# MocoMoco.net
KiCad netlist of a schematic drawn in EAGLE
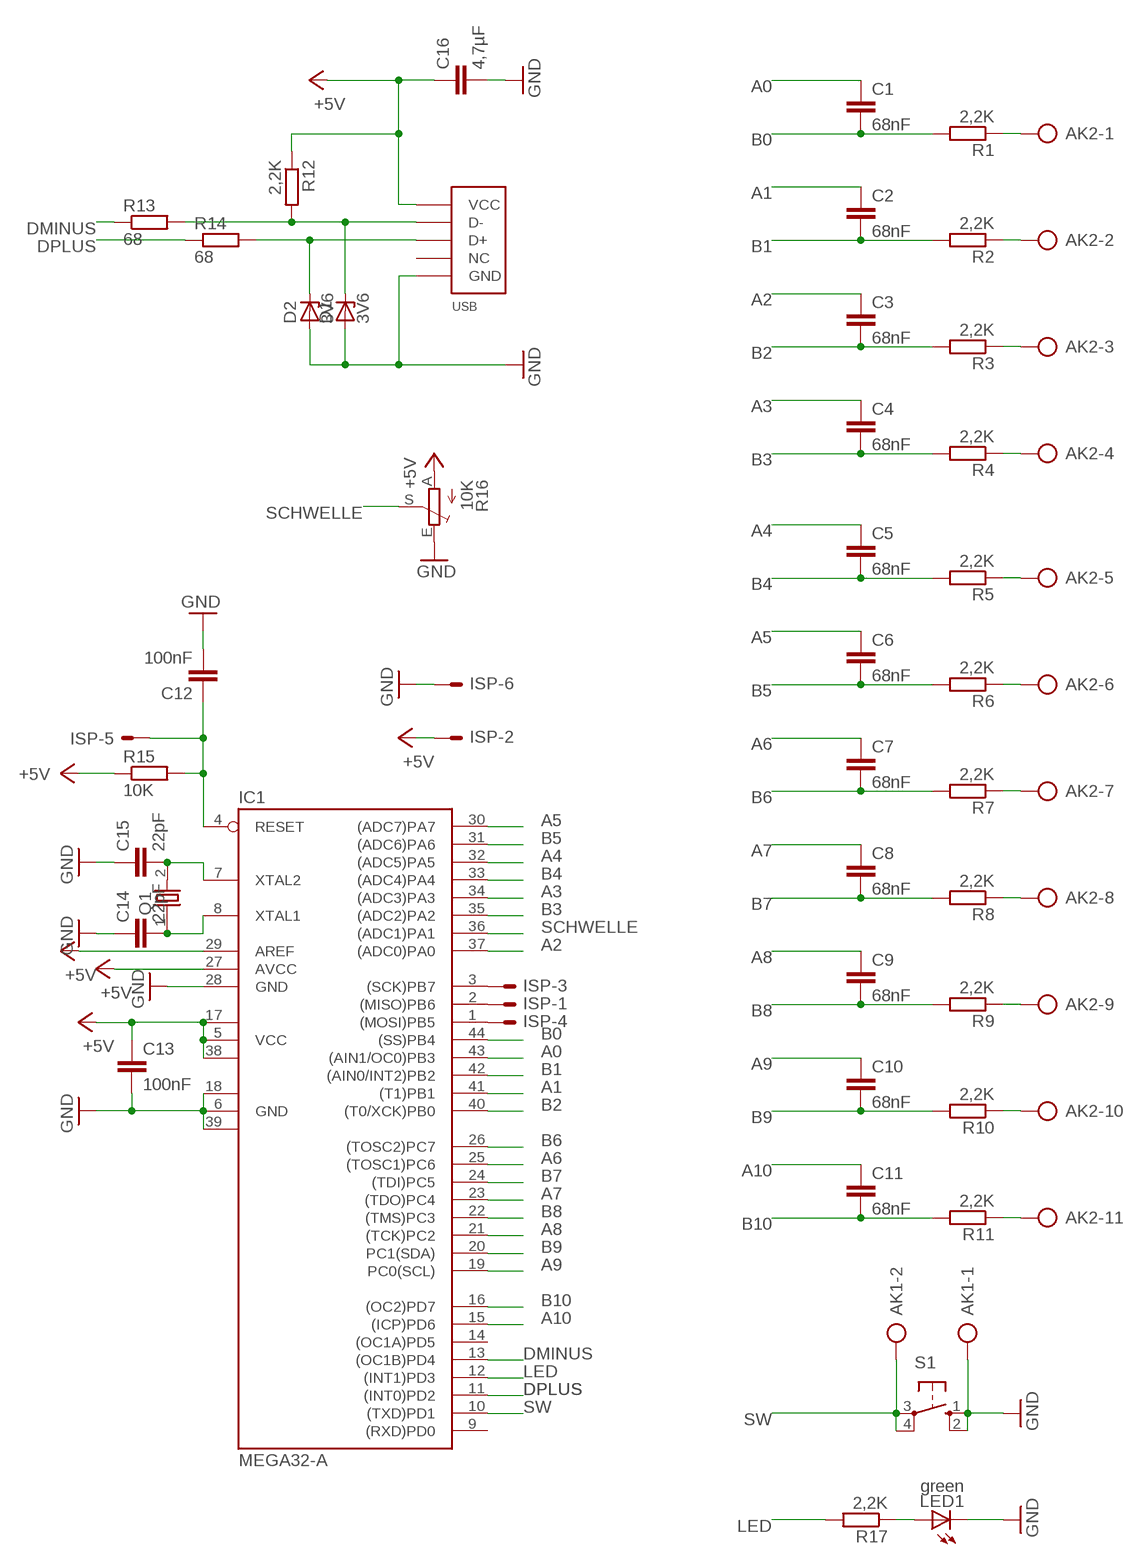
[diagram p0: schematic, sheet 1]

(export (version "E")
  (design (tool "Eeschema 10.0.6"))
  (components
    (comp (ref "AK1")
      (value "AK2")
      (footprint "eagle-import:AK_2")
      (libsource (lib "eagle-import") (part "AK2"))
    )
    (comp (ref "AK2")
      (value "AK11")
      (footprint "eagle-import:AK_11")
      (libsource (lib "eagle-import") (part "AK11"))
    )
    (comp (ref "C1")
      (value "68nF")
      (footprint "eagle-import:C0805K")
      (libsource (lib "eagle-import") (part "C-EUC0805K"))
    )
    (comp (ref "C2")
      (value "68nF")
      (footprint "eagle-import:C0805K")
      (libsource (lib "eagle-import") (part "C-EUC0805K"))
    )
    (comp (ref "C3")
      (value "68nF")
      (footprint "eagle-import:C0805K")
      (libsource (lib "eagle-import") (part "C-EUC0805K"))
    )
    (comp (ref "C4")
      (value "68nF")
      (footprint "eagle-import:C0805K")
      (libsource (lib "eagle-import") (part "C-EUC0805K"))
    )
    (comp (ref "C5")
      (value "68nF")
      (footprint "eagle-import:C0805K")
      (libsource (lib "eagle-import") (part "C-EUC0805K"))
    )
    (comp (ref "C6")
      (value "68nF")
      (footprint "eagle-import:C0805K")
      (libsource (lib "eagle-import") (part "C-EUC0805K"))
    )
    (comp (ref "C7")
      (value "68nF")
      (footprint "eagle-import:C0805K")
      (libsource (lib "eagle-import") (part "C-EUC0805K"))
    )
    (comp (ref "C8")
      (value "68nF")
      (footprint "eagle-import:C0805K")
      (libsource (lib "eagle-import") (part "C-EUC0805K"))
    )
    (comp (ref "C9")
      (value "68nF")
      (footprint "eagle-import:C0805K")
      (libsource (lib "eagle-import") (part "C-EUC0805K"))
    )
    (comp (ref "C10")
      (value "68nF")
      (footprint "eagle-import:C0805K")
      (libsource (lib "eagle-import") (part "C-EUC0805K"))
    )
    (comp (ref "C11")
      (value "68nF")
      (footprint "eagle-import:C0805K")
      (libsource (lib "eagle-import") (part "C-EUC0805K"))
    )
    (comp (ref "C12")
      (value "100nF")
      (footprint "eagle-import:C0805K")
      (libsource (lib "eagle-import") (part "C-EUC0805K"))
    )
    (comp (ref "C13")
      (value "100nF")
      (footprint "eagle-import:C0805K")
      (libsource (lib "eagle-import") (part "C-EUC0805K"))
    )
    (comp (ref "C14")
      (value "22pF")
      (footprint "eagle-import:C0805K")
      (libsource (lib "eagle-import") (part "C-EUC0805K"))
    )
    (comp (ref "C15")
      (value "22pF")
      (footprint "eagle-import:C0805K")
      (libsource (lib "eagle-import") (part "C-EUC0805K"))
    )
    (comp (ref "C16")
      (value "4,7µF")
      (footprint "eagle-import:C3216")
      (libsource (lib "eagle-import") (part "C-EUC3216"))
    )
    (comp (ref "D1")
      (value "3V6")
      (footprint "eagle-import:TO236")
      (libsource (lib "eagle-import") (part "BZX84CSMD"))
    )
    (comp (ref "D2")
      (value "3V6")
      (footprint "eagle-import:TO236")
      (libsource (lib "eagle-import") (part "BZX84CSMD"))
    )
    (comp (ref "IC1")
      (value "MEGA32-A")
      (footprint "eagle-import:TQFP44")
      (fields (field (name "MPN") "ATMEGA32-16AU"))
      (libsource (lib "eagle-import") (part "MEGA32-A"))
    )
    (comp (ref "ISP")
      (value "ML6E")
      (footprint "eagle-import:ML6")
      (libsource (lib "eagle-import") (part "ML6E"))
    )
    (comp (ref "LED1")
      (value "green")
      (footprint "eagle-import:CHIP-LED0603")
      (libsource (lib "eagle-import") (part "LEDCHIP-LED0603"))
    )
    (comp (ref "Q1")
      (value "HC-49/US")
      (footprint "eagle-import:HC49UP")
      (libsource (lib "eagle-import") (part "HC-49/US"))
    )
    (comp (ref "R1")
      (value "2,2K")
      (footprint "eagle-import:R0603")
      (libsource (lib "eagle-import") (part "R-EUR0603"))
    )
    (comp (ref "R2")
      (value "2,2K")
      (footprint "eagle-import:R0603")
      (libsource (lib "eagle-import") (part "R-EUR0603"))
    )
    (comp (ref "R3")
      (value "2,2K")
      (footprint "eagle-import:R0603")
      (libsource (lib "eagle-import") (part "R-EUR0603"))
    )
    (comp (ref "R4")
      (value "2,2K")
      (footprint "eagle-import:R0603")
      (libsource (lib "eagle-import") (part "R-EUR0603"))
    )
    (comp (ref "R5")
      (value "2,2K")
      (footprint "eagle-import:R0603")
      (libsource (lib "eagle-import") (part "R-EUR0603"))
    )
    (comp (ref "R6")
      (value "2,2K")
      (footprint "eagle-import:R0603")
      (libsource (lib "eagle-import") (part "R-EUR0603"))
    )
    (comp (ref "R7")
      (value "2,2K")
      (footprint "eagle-import:R0603")
      (libsource (lib "eagle-import") (part "R-EUR0603"))
    )
    (comp (ref "R8")
      (value "2,2K")
      (footprint "eagle-import:R0603")
      (libsource (lib "eagle-import") (part "R-EUR0603"))
    )
    (comp (ref "R9")
      (value "2,2K")
      (footprint "eagle-import:R0603")
      (libsource (lib "eagle-import") (part "R-EUR0603"))
    )
    (comp (ref "R10")
      (value "2,2K")
      (footprint "eagle-import:R0603")
      (libsource (lib "eagle-import") (part "R-EUR0603"))
    )
    (comp (ref "R11")
      (value "2,2K")
      (footprint "eagle-import:R0603")
      (libsource (lib "eagle-import") (part "R-EUR0603"))
    )
    (comp (ref "R12")
      (value "2,2K")
      (footprint "eagle-import:R0603")
      (libsource (lib "eagle-import") (part "R-EUR0603"))
    )
    (comp (ref "R13")
      (value "68")
      (footprint "eagle-import:R0603")
      (libsource (lib "eagle-import") (part "R-EUR0603"))
    )
    (comp (ref "R14")
      (value "68")
      (footprint "eagle-import:R0603")
      (libsource (lib "eagle-import") (part "R-EUR0603"))
    )
    (comp (ref "R15")
      (value "10K")
      (footprint "eagle-import:R0603")
      (libsource (lib "eagle-import") (part "R-EUR0603"))
    )
    (comp (ref "R16")
      (value "10K")
      (footprint "eagle-import:LI10")
      (libsource (lib "eagle-import") (part "TRIM_EU-LI10"))
    )
    (comp (ref "R17")
      (value "2,2K")
      (footprint "eagle-import:R0603")
      (libsource (lib "eagle-import") (part "R-EUR0603"))
    )
    (comp (ref "S1")
      (value "10-XX")
      (footprint "eagle-import:B3F-10XX")
      (fields (field (name "MPN") "B3F-1000"))
      (libsource (lib "eagle-import") (part "10-XX"))
    )
    (comp (ref "USB")
      (value "MICRO_USB")
      (footprint "eagle-import:MICRO_USB_A01SB141B1-292")
      (libsource (lib "eagle-import") (part "MICRO_USB"))
    )
  )
  (nets
    (net (code "1") (name "+5V") (class "Default")
      (node (ref "C13") (pin "1") (pinfunction "1_1") (pintype "passive"))
      (node (ref "C16") (pin "1") (pinfunction "1_1") (pintype "passive"))
      (node (ref "IC1") (pin "17") (pinfunction "VCC1_17") (pintype "power_in"))
      (node (ref "IC1") (pin "27") (pinfunction "AVCC_27") (pintype "power_in"))
      (node (ref "IC1") (pin "29") (pinfunction "AREF_29") (pintype "passive"))
      (node (ref "IC1") (pin "38") (pinfunction "VCC2_38") (pintype "power_in"))
      (node (ref "IC1") (pin "5") (pinfunction "VCC_5") (pintype "power_in"))
      (node (ref "ISP") (pin "2") (pinfunction "S_2") (pintype "passive"))
      (node (ref "R12") (pin "1") (pinfunction "1_1") (pintype "passive"))
      (node (ref "R15") (pin "1") (pinfunction "1_1") (pintype "passive"))
      (node (ref "R16") (pin "A") (pinfunction "A_A") (pintype "passive"))
      (node (ref "USB") (pin "P$1") (pinfunction "VCC_P$1") (pintype "bidirectional"))
    )
    (net (code "2") (name "/A0") (class "Default")
      (node (ref "C1") (pin "1") (pinfunction "1_1") (pintype "passive"))
      (node (ref "IC1") (pin "43") (pinfunction "(AIN1/OC0)PB3_43") (pintype "bidirectional"))
    )
    (net (code "3") (name "/A1") (class "Default")
      (node (ref "C2") (pin "1") (pinfunction "1_1") (pintype "passive"))
      (node (ref "IC1") (pin "41") (pinfunction "(T1)PB1_41") (pintype "bidirectional"))
    )
    (net (code "4") (name "/A2") (class "Default")
      (node (ref "C3") (pin "1") (pinfunction "1_1") (pintype "passive"))
      (node (ref "IC1") (pin "37") (pinfunction "(ADC0)PA0_37") (pintype "bidirectional"))
    )
    (net (code "5") (name "/A3") (class "Default")
      (node (ref "C4") (pin "1") (pinfunction "1_1") (pintype "passive"))
      (node (ref "IC1") (pin "34") (pinfunction "(ADC3)PA3_34") (pintype "bidirectional"))
    )
    (net (code "6") (name "/A4") (class "Default")
      (node (ref "C5") (pin "1") (pinfunction "1_1") (pintype "passive"))
      (node (ref "IC1") (pin "32") (pinfunction "(ADC5)PA5_32") (pintype "bidirectional"))
    )
    (net (code "7") (name "/A5") (class "Default")
      (node (ref "C6") (pin "1") (pinfunction "1_1") (pintype "passive"))
      (node (ref "IC1") (pin "30") (pinfunction "(ADC7)PA7_30") (pintype "bidirectional"))
    )
    (net (code "8") (name "/A6") (class "Default")
      (node (ref "C7") (pin "1") (pinfunction "1_1") (pintype "passive"))
      (node (ref "IC1") (pin "25") (pinfunction "(TOSC1)PC6_25") (pintype "bidirectional"))
    )
    (net (code "9") (name "/A7") (class "Default")
      (node (ref "C8") (pin "1") (pinfunction "1_1") (pintype "passive"))
      (node (ref "IC1") (pin "23") (pinfunction "(TDO)PC4_23") (pintype "bidirectional"))
    )
    (net (code "10") (name "/A8") (class "Default")
      (node (ref "C9") (pin "1") (pinfunction "1_1") (pintype "passive"))
      (node (ref "IC1") (pin "21") (pinfunction "(TCK)PC2_21") (pintype "bidirectional"))
    )
    (net (code "11") (name "/A9") (class "Default")
      (node (ref "C10") (pin "1") (pinfunction "1_1") (pintype "passive"))
      (node (ref "IC1") (pin "19") (pinfunction "PC0(SCL)_19") (pintype "bidirectional"))
    )
    (net (code "12") (name "/A10") (class "Default")
      (node (ref "C11") (pin "1") (pinfunction "1_1") (pintype "passive"))
      (node (ref "IC1") (pin "15") (pinfunction "(ICP)PD6_15") (pintype "bidirectional"))
    )
    (net (code "13") (name "/B0") (class "Default")
      (node (ref "C1") (pin "2") (pinfunction "2_2") (pintype "passive"))
      (node (ref "IC1") (pin "44") (pinfunction "(SS)PB4_44") (pintype "bidirectional"))
      (node (ref "R1") (pin "2") (pinfunction "2_2") (pintype "passive"))
    )
    (net (code "14") (name "/B1") (class "Default")
      (node (ref "C2") (pin "2") (pinfunction "2_2") (pintype "passive"))
      (node (ref "IC1") (pin "42") (pinfunction "(AIN0/INT2)PB2_42") (pintype "bidirectional"))
      (node (ref "R2") (pin "2") (pinfunction "2_2") (pintype "passive"))
    )
    (net (code "15") (name "/B2") (class "Default")
      (node (ref "C3") (pin "2") (pinfunction "2_2") (pintype "passive"))
      (node (ref "IC1") (pin "40") (pinfunction "(T0/XCK)PB0_40") (pintype "bidirectional"))
      (node (ref "R3") (pin "2") (pinfunction "2_2") (pintype "passive"))
    )
    (net (code "16") (name "/B3") (class "Default")
      (node (ref "C4") (pin "2") (pinfunction "2_2") (pintype "passive"))
      (node (ref "IC1") (pin "35") (pinfunction "(ADC2)PA2_35") (pintype "bidirectional"))
      (node (ref "R4") (pin "2") (pinfunction "2_2") (pintype "passive"))
    )
    (net (code "17") (name "/B4") (class "Default")
      (node (ref "C5") (pin "2") (pinfunction "2_2") (pintype "passive"))
      (node (ref "IC1") (pin "33") (pinfunction "(ADC4)PA4_33") (pintype "bidirectional"))
      (node (ref "R5") (pin "2") (pinfunction "2_2") (pintype "passive"))
    )
    (net (code "18") (name "/B5") (class "Default")
      (node (ref "C6") (pin "2") (pinfunction "2_2") (pintype "passive"))
      (node (ref "IC1") (pin "31") (pinfunction "(ADC6)PA6_31") (pintype "bidirectional"))
      (node (ref "R6") (pin "2") (pinfunction "2_2") (pintype "passive"))
    )
    (net (code "19") (name "/B6") (class "Default")
      (node (ref "C7") (pin "2") (pinfunction "2_2") (pintype "passive"))
      (node (ref "IC1") (pin "26") (pinfunction "(TOSC2)PC7_26") (pintype "bidirectional"))
      (node (ref "R7") (pin "2") (pinfunction "2_2") (pintype "passive"))
    )
    (net (code "20") (name "/B7") (class "Default")
      (node (ref "C8") (pin "2") (pinfunction "2_2") (pintype "passive"))
      (node (ref "IC1") (pin "24") (pinfunction "(TDI)PC5_24") (pintype "bidirectional"))
      (node (ref "R8") (pin "2") (pinfunction "2_2") (pintype "passive"))
    )
    (net (code "21") (name "/B8") (class "Default")
      (node (ref "C9") (pin "2") (pinfunction "2_2") (pintype "passive"))
      (node (ref "IC1") (pin "22") (pinfunction "(TMS)PC3_22") (pintype "bidirectional"))
      (node (ref "R9") (pin "2") (pinfunction "2_2") (pintype "passive"))
    )
    (net (code "22") (name "/B9") (class "Default")
      (node (ref "C10") (pin "2") (pinfunction "2_2") (pintype "passive"))
      (node (ref "IC1") (pin "20") (pinfunction "PC1(SDA)_20") (pintype "bidirectional"))
      (node (ref "R10") (pin "2") (pinfunction "2_2") (pintype "passive"))
    )
    (net (code "23") (name "/B10") (class "Default")
      (node (ref "C11") (pin "2") (pinfunction "2_2") (pintype "passive"))
      (node (ref "IC1") (pin "16") (pinfunction "(OC2)PD7_16") (pintype "bidirectional"))
      (node (ref "R11") (pin "2") (pinfunction "2_2") (pintype "passive"))
    )
    (net (code "24") (name "/DMINUS") (class "Default")
      (node (ref "IC1") (pin "13") (pinfunction "(OC1B)PD4_13") (pintype "bidirectional"))
      (node (ref "R13") (pin "1") (pinfunction "1_1") (pintype "passive"))
    )
    (net (code "25") (name "/DPLUS") (class "Default")
      (node (ref "IC1") (pin "11") (pinfunction "(INT0)PD2_11") (pintype "bidirectional"))
      (node (ref "R14") (pin "1") (pinfunction "1_1") (pintype "passive"))
    )
    (net (code "26") (name "/LED") (class "Default")
      (node (ref "IC1") (pin "12") (pinfunction "(INT1)PD3_12") (pintype "bidirectional"))
      (node (ref "R17") (pin "2") (pinfunction "2_2") (pintype "passive"))
    )
    (net (code "27") (name "/SCHWELLE") (class "Default")
      (node (ref "IC1") (pin "36") (pinfunction "(ADC1)PA1_36") (pintype "bidirectional"))
      (node (ref "R16") (pin "S") (pinfunction "S_S") (pintype "passive"))
    )
    (net (code "28") (name "/SW") (class "Default")
      (node (ref "AK1") (pin "2") (pinfunction "KL_2") (pintype "passive"))
      (node (ref "IC1") (pin "10") (pinfunction "(TXD)PD1_10") (pintype "bidirectional"))
      (node (ref "S1") (pin "3") (pinfunction "P_3") (pintype "passive"))
      (node (ref "S1") (pin "4") (pinfunction "P1_4") (pintype "passive"))
    )
    (net (code "29") (name "GND") (class "Default")
      (node (ref "AK1") (pin "1") (pinfunction "KL_1") (pintype "passive"))
      (node (ref "C12") (pin "2") (pinfunction "2_2") (pintype "passive"))
      (node (ref "C13") (pin "2") (pinfunction "2_2") (pintype "passive"))
      (node (ref "C14") (pin "1") (pinfunction "1_1") (pintype "passive"))
      (node (ref "C15") (pin "1") (pinfunction "1_1") (pintype "passive"))
      (node (ref "C16") (pin "2") (pinfunction "2_2") (pintype "passive"))
      (node (ref "D1") (pin "A") (pinfunction "A_A") (pintype "passive"))
      (node (ref "D2") (pin "A") (pinfunction "A_A") (pintype "passive"))
      (node (ref "IC1") (pin "18") (pinfunction "GND1_18") (pintype "power_in"))
      (node (ref "IC1") (pin "28") (pinfunction "GND_28") (pintype "power_in"))
      (node (ref "IC1") (pin "39") (pinfunction "GND2_39") (pintype "power_in"))
      (node (ref "IC1") (pin "6") (pinfunction "GND_6") (pintype "power_in"))
      (node (ref "ISP") (pin "6") (pinfunction "S_6") (pintype "passive"))
      (node (ref "LED1") (pin "C") (pinfunction "C_C") (pintype "passive"))
      (node (ref "R16") (pin "E") (pinfunction "E_E") (pintype "passive"))
      (node (ref "S1") (pin "1") (pinfunction "S_1") (pintype "passive"))
      (node (ref "S1") (pin "2") (pinfunction "S1_2") (pintype "passive"))
      (node (ref "USB") (pin "P$5") (pinfunction "GND_P$5") (pintype "bidirectional"))
    )
    (net (code "30") (name "Net-(AK2A-KL)") (class "Default")
      (node (ref "AK2") (pin "1") (pinfunction "KL_1") (pintype "passive"))
      (node (ref "R1") (pin "1") (pinfunction "1_1") (pintype "passive"))
    )
    (net (code "31") (name "Net-(AK2B-KL)") (class "Default")
      (node (ref "AK2") (pin "10") (pinfunction "KL_10") (pintype "passive"))
      (node (ref "R10") (pin "1") (pinfunction "1_1") (pintype "passive"))
    )
    (net (code "32") (name "Net-(AK2C-KL)") (class "Default")
      (node (ref "AK2") (pin "11") (pinfunction "KL_11") (pintype "passive"))
      (node (ref "R11") (pin "1") (pinfunction "1_1") (pintype "passive"))
    )
    (net (code "33") (name "Net-(AK2D-KL)") (class "Default")
      (node (ref "AK2") (pin "2") (pinfunction "KL_2") (pintype "passive"))
      (node (ref "R2") (pin "1") (pinfunction "1_1") (pintype "passive"))
    )
    (net (code "34") (name "Net-(AK2E-KL)") (class "Default")
      (node (ref "AK2") (pin "3") (pinfunction "KL_3") (pintype "passive"))
      (node (ref "R3") (pin "1") (pinfunction "1_1") (pintype "passive"))
    )
    (net (code "35") (name "Net-(AK2F-KL)") (class "Default")
      (node (ref "AK2") (pin "4") (pinfunction "KL_4") (pintype "passive"))
      (node (ref "R4") (pin "1") (pinfunction "1_1") (pintype "passive"))
    )
    (net (code "36") (name "Net-(AK2G-KL)") (class "Default")
      (node (ref "AK2") (pin "5") (pinfunction "KL_5") (pintype "passive"))
      (node (ref "R5") (pin "1") (pinfunction "1_1") (pintype "passive"))
    )
    (net (code "37") (name "Net-(AK2H-KL)") (class "Default")
      (node (ref "AK2") (pin "6") (pinfunction "KL_6") (pintype "passive"))
      (node (ref "R6") (pin "1") (pinfunction "1_1") (pintype "passive"))
    )
    (net (code "38") (name "Net-(AK2I-KL)") (class "Default")
      (node (ref "AK2") (pin "7") (pinfunction "KL_7") (pintype "passive"))
      (node (ref "R7") (pin "1") (pinfunction "1_1") (pintype "passive"))
    )
    (net (code "39") (name "Net-(AK2J-KL)") (class "Default")
      (node (ref "AK2") (pin "8") (pinfunction "KL_8") (pintype "passive"))
      (node (ref "R8") (pin "1") (pinfunction "1_1") (pintype "passive"))
    )
    (net (code "40") (name "Net-(AK2K-KL)") (class "Default")
      (node (ref "AK2") (pin "9") (pinfunction "KL_9") (pintype "passive"))
      (node (ref "R9") (pin "1") (pinfunction "1_1") (pintype "passive"))
    )
    (net (code "41") (name "Net-(IC1-(MISO)PB6)") (class "Default")
      (node (ref "IC1") (pin "2") (pinfunction "(MISO)PB6_2") (pintype "bidirectional"))
      (node (ref "ISP") (pin "1") (pinfunction "S_1") (pintype "passive"))
    )
    (net (code "42") (name "Net-(IC1-(MOSI)PB5)") (class "Default")
      (node (ref "IC1") (pin "1") (pinfunction "(MOSI)PB5_1") (pintype "bidirectional"))
      (node (ref "ISP") (pin "4") (pinfunction "S_4") (pintype "passive"))
    )
    (net (code "43") (name "Net-(IC1-(SCK)PB7)") (class "Default")
      (node (ref "IC1") (pin "3") (pinfunction "(SCK)PB7_3") (pintype "bidirectional"))
      (node (ref "ISP") (pin "3") (pinfunction "S_3") (pintype "passive"))
    )
    (net (code "44") (name "Net-(IC1-RESET)") (class "Default")
      (node (ref "C12") (pin "1") (pinfunction "1_1") (pintype "passive"))
      (node (ref "IC1") (pin "4") (pinfunction "RESET_4") (pintype "input"))
      (node (ref "ISP") (pin "5") (pinfunction "S_5") (pintype "passive"))
      (node (ref "R15") (pin "2") (pinfunction "2_2") (pintype "passive"))
    )
    (net (code "45") (name "Net-(IC1-XTAL1)") (class "Default")
      (node (ref "C14") (pin "2") (pinfunction "2_2") (pintype "passive"))
      (node (ref "IC1") (pin "8") (pinfunction "XTAL1_8") (pintype "bidirectional"))
      (node (ref "Q1") (pin "1") (pinfunction "1_1") (pintype "passive"))
    )
    (net (code "46") (name "Net-(IC1-XTAL2)") (class "Default")
      (node (ref "C15") (pin "2") (pinfunction "2_2") (pintype "passive"))
      (node (ref "IC1") (pin "7") (pinfunction "XTAL2_7") (pintype "bidirectional"))
      (node (ref "Q1") (pin "2") (pinfunction "2_2") (pintype "passive"))
    )
    (net (code "47") (name "Net-(LED1-PadA)") (class "Default")
      (node (ref "LED1") (pin "A") (pinfunction "A_A") (pintype "passive"))
      (node (ref "R17") (pin "1") (pinfunction "1_1") (pintype "passive"))
    )
    (net (code "48") (name "Net-(USB-D+)") (class "Default")
      (node (ref "D2") (pin "C") (pinfunction "C_C") (pintype "passive"))
      (node (ref "R14") (pin "2") (pinfunction "2_2") (pintype "passive"))
      (node (ref "USB") (pin "P$3") (pinfunction "D+_P$3") (pintype "bidirectional"))
    )
    (net (code "49") (name "Net-(USB-D-)") (class "Default")
      (node (ref "D1") (pin "C") (pinfunction "C_C") (pintype "passive"))
      (node (ref "R12") (pin "2") (pinfunction "2_2") (pintype "passive"))
      (node (ref "R13") (pin "2") (pinfunction "2_2") (pintype "passive"))
      (node (ref "USB") (pin "P$2") (pinfunction "D-_P$2") (pintype "bidirectional"))
    )
    (net (code "50") (name "unconnected-(IC1-(OC1A)PD5-Pad14)") (class "Default")
      (node (ref "IC1") (pin "14") (pinfunction "(OC1A)PD5_14") (pintype "bidirectional"))
    )
    (net (code "51") (name "unconnected-(IC1-(RXD)PD0-Pad9)") (class "Default")
      (node (ref "IC1") (pin "9") (pinfunction "(RXD)PD0_9") (pintype "bidirectional"))
    )
    (net (code "52") (name "unconnected-(USB-NC-PadP$4)") (class "Default")
      (node (ref "USB") (pin "P$4") (pinfunction "NC_P$4") (pintype "bidirectional"))
    )
  )
)
